# T01_411_Synth_v3.net
KiCad netlist of a schematic drawn in EAGLE
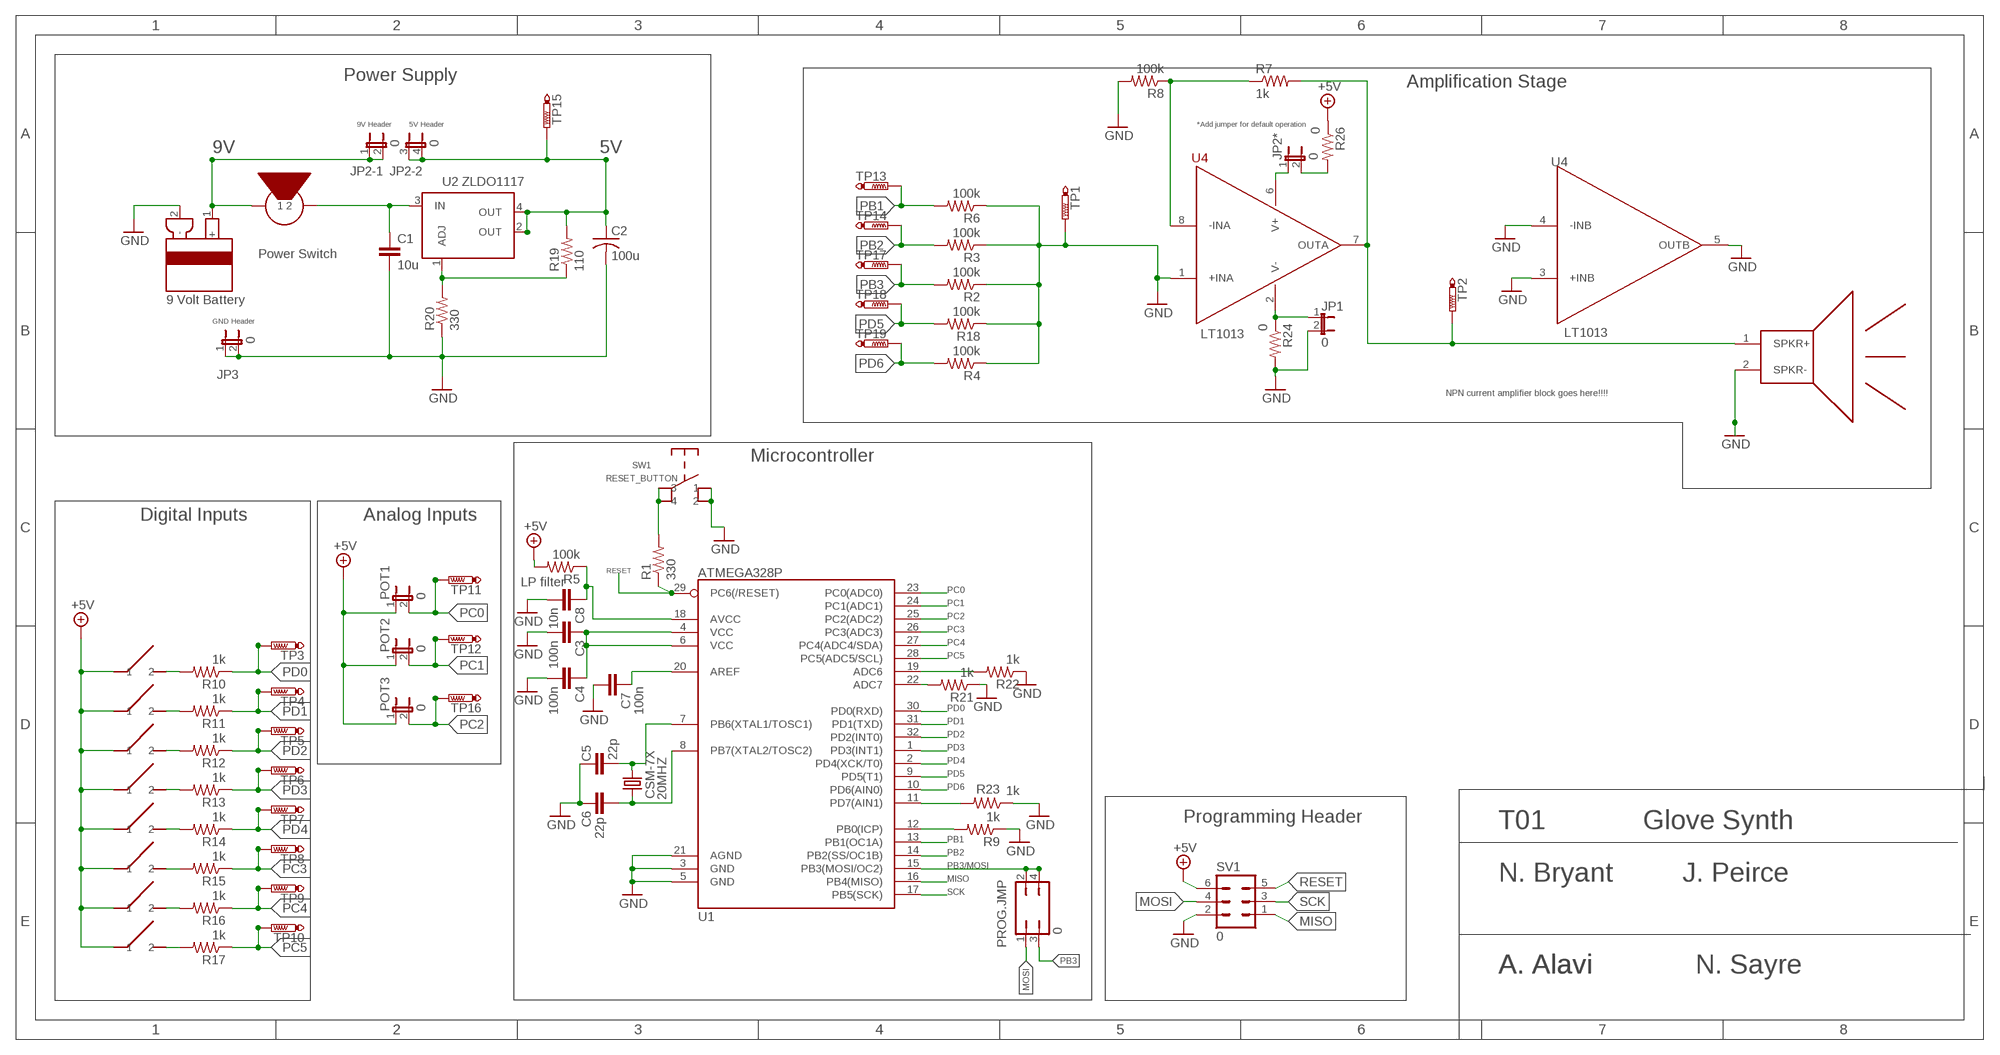
[diagram p0: schematic, sheet 1]

(export (version "E")
  (design (tool "Eeschema 10.0.6"))
  (components
    (comp (ref "20MHZ")
      (value "CSM-7X")
      (footprint "eagle-import:CSM-7X-DU")
      (libsource (lib "eagle-import") (part "CSM-7X-DU"))
    )
    (comp (ref "C1")
      (value "10u")
      (footprint "eagle-import:0603-CAP")
      (libsource (lib "eagle-import") (part "CAP0603-CAP"))
    )
    (comp (ref "C2")
      (value "100u")
      (footprint "eagle-import:C075-042X103")
      (libsource (lib "eagle-import") (part "C-US075-042X103"))
    )
    (comp (ref "C3")
      (value "100n")
      (footprint "eagle-import:0603-CAP")
      (libsource (lib "eagle-import") (part "CAP0603-CAP"))
    )
    (comp (ref "C4")
      (value "100n")
      (footprint "eagle-import:0603-CAP")
      (libsource (lib "eagle-import") (part "CAP0603-CAP"))
    )
    (comp (ref "C5")
      (value "22p")
      (footprint "eagle-import:0603-CAP")
      (libsource (lib "eagle-import") (part "CAP0603-CAP"))
    )
    (comp (ref "C6")
      (value "22p")
      (footprint "eagle-import:0603-CAP")
      (libsource (lib "eagle-import") (part "CAP0603-CAP"))
    )
    (comp (ref "C7")
      (value "100n")
      (footprint "eagle-import:0603-CAP")
      (libsource (lib "eagle-import") (part "CAP0603-CAP"))
    )
    (comp (ref "C8")
      (value "10n")
      (footprint "eagle-import:0603-CAP")
      (libsource (lib "eagle-import") (part "CAP0603-CAP"))
    )
    (comp (ref "JP1")
      (value "0")
      (footprint "eagle-import:JP1")
      (libsource (lib "eagle-import") (part "JP1E"))
    )
    (comp (ref "JP2")
      (value "0")
      (footprint "eagle-import:JP2Q")
      (libsource (lib "eagle-import") (part "JP2QE"))
    )
    (comp (ref "JP2*")
      (value "0")
      (footprint "eagle-import:JP1")
      (libsource (lib "eagle-import") (part "JP1E"))
    )
    (comp (ref "JP3")
      (value "0")
      (footprint "eagle-import:JP1")
      (libsource (lib "eagle-import") (part "JP1E"))
    )
    (comp (ref "POT1")
      (value "0")
      (footprint "eagle-import:JP1")
      (libsource (lib "eagle-import") (part "JP1E"))
    )
    (comp (ref "POT2")
      (value "0")
      (footprint "eagle-import:JP1")
      (libsource (lib "eagle-import") (part "JP1E"))
    )
    (comp (ref "POT3")
      (value "0")
      (footprint "eagle-import:JP1")
      (libsource (lib "eagle-import") (part "JP1E"))
    )
    (comp (ref "PROG.JMP")
      (value "0")
      (footprint "eagle-import:JP2Q")
      (libsource (lib "eagle-import") (part "JP2Q"))
    )
    (comp (ref "R1")
      (value "330")
      (footprint "eagle-import:0603-RES")
      (libsource (lib "eagle-import") (part "RESISTOR0603"))
    )
    (comp (ref "R2")
      (value "100k")
      (footprint "eagle-import:0603-RES")
      (libsource (lib "eagle-import") (part "RESISTOR0603"))
    )
    (comp (ref "R3")
      (value "100k")
      (footprint "eagle-import:0603-RES")
      (libsource (lib "eagle-import") (part "RESISTOR0603"))
    )
    (comp (ref "R4")
      (value "100k")
      (footprint "eagle-import:0603-RES")
      (libsource (lib "eagle-import") (part "RESISTOR0603"))
    )
    (comp (ref "R5")
      (value "100k")
      (footprint "eagle-import:0603-RES")
      (libsource (lib "eagle-import") (part "RESISTOR0603"))
    )
    (comp (ref "R6")
      (value "100k")
      (footprint "eagle-import:0603-RES")
      (libsource (lib "eagle-import") (part "RESISTOR0603"))
    )
    (comp (ref "R7")
      (value "1k")
      (footprint "eagle-import:0603-RES")
      (libsource (lib "eagle-import") (part "RESISTOR0603"))
    )
    (comp (ref "R8")
      (value "100k")
      (footprint "eagle-import:0603-RES")
      (libsource (lib "eagle-import") (part "RESISTOR0603"))
    )
    (comp (ref "R9")
      (value "1k")
      (footprint "eagle-import:0603-RES")
      (libsource (lib "eagle-import") (part "RESISTOR0603"))
    )
    (comp (ref "R10")
      (value "1k")
      (footprint "eagle-import:0603-RES")
      (libsource (lib "eagle-import") (part "RESISTOR0603"))
    )
    (comp (ref "R11")
      (value "1k")
      (footprint "eagle-import:0603-RES")
      (libsource (lib "eagle-import") (part "RESISTOR0603"))
    )
    (comp (ref "R12")
      (value "1k")
      (footprint "eagle-import:0603-RES")
      (libsource (lib "eagle-import") (part "RESISTOR0603"))
    )
    (comp (ref "R13")
      (value "1k")
      (footprint "eagle-import:0603-RES")
      (libsource (lib "eagle-import") (part "RESISTOR0603"))
    )
    (comp (ref "R14")
      (value "1k")
      (footprint "eagle-import:0603-RES")
      (libsource (lib "eagle-import") (part "RESISTOR0603"))
    )
    (comp (ref "R15")
      (value "1k")
      (footprint "eagle-import:0603-RES")
      (libsource (lib "eagle-import") (part "RESISTOR0603"))
    )
    (comp (ref "R16")
      (value "1k")
      (footprint "eagle-import:0603-RES")
      (libsource (lib "eagle-import") (part "RESISTOR0603"))
    )
    (comp (ref "R17")
      (value "1k")
      (footprint "eagle-import:0603-RES")
      (libsource (lib "eagle-import") (part "RESISTOR0603"))
    )
    (comp (ref "R18")
      (value "100k")
      (footprint "eagle-import:0603-RES")
      (libsource (lib "eagle-import") (part "RESISTOR0603"))
    )
    (comp (ref "R19")
      (value "110")
      (footprint "eagle-import:0603-RES")
      (libsource (lib "eagle-import") (part "RESISTOR0603"))
    )
    (comp (ref "R20")
      (value "330")
      (footprint "eagle-import:0603-RES")
      (libsource (lib "eagle-import") (part "RESISTOR0603"))
    )
    (comp (ref "R21")
      (value "1k")
      (footprint "eagle-import:0603-RES")
      (libsource (lib "eagle-import") (part "RESISTOR0603"))
    )
    (comp (ref "R22")
      (value "1k")
      (footprint "eagle-import:0603-RES")
      (libsource (lib "eagle-import") (part "RESISTOR0603"))
    )
    (comp (ref "R23")
      (value "1k")
      (footprint "eagle-import:0603-RES")
      (libsource (lib "eagle-import") (part "RESISTOR0603"))
    )
    (comp (ref "R24")
      (value "0")
      (footprint "eagle-import:0603-RES")
      (libsource (lib "eagle-import") (part "RESISTOR0603"))
    )
    (comp (ref "R26")
      (value "0")
      (footprint "eagle-import:0603-RES")
      (libsource (lib "eagle-import") (part "RESISTOR0603"))
    )
    (comp (ref "SV1")
      (value "0")
      (footprint "eagle-import:MA03-2")
      (libsource (lib "eagle-import") (part "MA03-2"))
    )
    (comp (ref "SW1")
      (value "RESET_BUTTON")
      (footprint "eagle-import:RESET_BUTTON")
      (libsource (lib "eagle-import") (part "RESET_BUTTON"))
    )
    (comp (ref "TP1")
      (value "PTR1B2,54")
      (footprint "eagle-import:B2,54")
      (libsource (lib "eagle-import") (part "PTR1B2,54"))
    )
    (comp (ref "TP2")
      (value "PTR1B2,54")
      (footprint "eagle-import:B2,54")
      (libsource (lib "eagle-import") (part "PTR1B2,54"))
    )
    (comp (ref "TP3")
      (value "PTR1B2,54")
      (footprint "eagle-import:B2,54")
      (libsource (lib "eagle-import") (part "PTR1B2,54"))
    )
    (comp (ref "TP4")
      (value "PTR1B2,54")
      (footprint "eagle-import:B2,54")
      (libsource (lib "eagle-import") (part "PTR1B2,54"))
    )
    (comp (ref "TP5")
      (value "PTR1B2,54")
      (footprint "eagle-import:B2,54")
      (libsource (lib "eagle-import") (part "PTR1B2,54"))
    )
    (comp (ref "TP6")
      (value "PTR1B2,54")
      (footprint "eagle-import:B2,54")
      (libsource (lib "eagle-import") (part "PTR1B2,54"))
    )
    (comp (ref "TP7")
      (value "PTR1B2,54")
      (footprint "eagle-import:B2,54")
      (libsource (lib "eagle-import") (part "PTR1B2,54"))
    )
    (comp (ref "TP8")
      (value "PTR1B2,54")
      (footprint "eagle-import:B2,54")
      (libsource (lib "eagle-import") (part "PTR1B2,54"))
    )
    (comp (ref "TP9")
      (value "PTR1B2,54")
      (footprint "eagle-import:B2,54")
      (libsource (lib "eagle-import") (part "PTR1B2,54"))
    )
    (comp (ref "TP10")
      (value "PTR1B2,54")
      (footprint "eagle-import:B2,54")
      (libsource (lib "eagle-import") (part "PTR1B2,54"))
    )
    (comp (ref "TP11")
      (value "PTR1B2,54")
      (footprint "eagle-import:B2,54")
      (libsource (lib "eagle-import") (part "PTR1B2,54"))
    )
    (comp (ref "TP12")
      (value "PTR1B2,54")
      (footprint "eagle-import:B2,54")
      (libsource (lib "eagle-import") (part "PTR1B2,54"))
    )
    (comp (ref "TP13")
      (value "PTR1B2,54")
      (footprint "eagle-import:B2,54")
      (libsource (lib "eagle-import") (part "PTR1B2,54"))
    )
    (comp (ref "TP14")
      (value "PTR1B2,54")
      (footprint "eagle-import:B2,54")
      (libsource (lib "eagle-import") (part "PTR1B2,54"))
    )
    (comp (ref "TP15")
      (value "PTR1B2,54")
      (footprint "eagle-import:B2,54")
      (libsource (lib "eagle-import") (part "PTR1B2,54"))
    )
    (comp (ref "TP16")
      (value "PTR1B2,54")
      (footprint "eagle-import:B2,54")
      (libsource (lib "eagle-import") (part "PTR1B2,54"))
    )
    (comp (ref "TP17")
      (value "PTR1B2,54")
      (footprint "eagle-import:B2,54")
      (libsource (lib "eagle-import") (part "PTR1B2,54"))
    )
    (comp (ref "TP18")
      (value "PTR1B2,54")
      (footprint "eagle-import:B2,54")
      (libsource (lib "eagle-import") (part "PTR1B2,54"))
    )
    (comp (ref "TP19")
      (value "PTR1B2,54")
      (footprint "eagle-import:B2,54")
      (libsource (lib "eagle-import") (part "PTR1B2,54"))
    )
    (comp (ref "U$1")
      (value "SPEAKER")
      (footprint "eagle-import:JP1")
      (libsource (lib "eagle-import") (part "SPEAKER"))
    )
    (comp (ref "U$7")
      (value "POWER_SWITCH")
      (footprint "eagle-import:JP1")
      (libsource (lib "eagle-import") (part "POWER_SWITCH"))
    )
    (comp (ref "U$8")
      (value "9VOLTBATTERY")
      (footprint "eagle-import:JP1")
      (libsource (lib "eagle-import") (part "9VOLTBATTERY"))
    )
    (comp (ref "U$11")
      (value "FINGER_BUTTON")
      (footprint "eagle-import:JP1")
      (libsource (lib "eagle-import") (part "FINGER_BUTTON"))
    )
    (comp (ref "U$12")
      (value "FINGER_BUTTON")
      (footprint "eagle-import:JP1")
      (libsource (lib "eagle-import") (part "FINGER_BUTTON"))
    )
    (comp (ref "U$13")
      (value "FINGER_BUTTON")
      (footprint "eagle-import:JP1")
      (libsource (lib "eagle-import") (part "FINGER_BUTTON"))
    )
    (comp (ref "U$14")
      (value "FINGER_BUTTON")
      (footprint "eagle-import:JP1")
      (libsource (lib "eagle-import") (part "FINGER_BUTTON"))
    )
    (comp (ref "U$15")
      (value "FINGER_BUTTON")
      (footprint "eagle-import:JP1")
      (libsource (lib "eagle-import") (part "FINGER_BUTTON"))
    )
    (comp (ref "U$16")
      (value "FINGER_BUTTON")
      (footprint "eagle-import:JP1")
      (libsource (lib "eagle-import") (part "FINGER_BUTTON"))
    )
    (comp (ref "U$17")
      (value "FINGER_BUTTON")
      (footprint "eagle-import:JP1")
      (libsource (lib "eagle-import") (part "FINGER_BUTTON"))
    )
    (comp (ref "U$18")
      (value "FINGER_BUTTON")
      (footprint "eagle-import:JP1")
      (libsource (lib "eagle-import") (part "FINGER_BUTTON"))
    )
    (comp (ref "U1")
      (value "ATMEGA328P")
      (footprint "eagle-import:TQFP32-08")
      (libsource (lib "eagle-import") (part "ATMEGA328_SMT"))
    )
    (comp (ref "U2")
      (value "ZLDO1117")
      (footprint "eagle-import:SOT223")
      (libsource (lib "eagle-import") (part "ZLDO1117"))
    )
    (comp (ref "U4")
      (value "LT1013")
      (footprint "eagle-import:SO08")
      (libsource (lib "eagle-import") (part "LT1013"))
    )
  )
  (nets
    (net (code "1") (name "+5V") (class "Default")
      (node (ref "POT1") (pin "1") (pinfunction "1_1") (pintype "passive"))
      (node (ref "POT2") (pin "1") (pinfunction "1_1") (pintype "passive"))
      (node (ref "POT3") (pin "1") (pinfunction "1_1") (pintype "passive"))
      (node (ref "R26") (pin "1") (pinfunction "1_1") (pintype "passive"))
      (node (ref "R5") (pin "2") (pinfunction "2_2") (pintype "passive"))
      (node (ref "SV1") (pin "6") (pinfunction "6_6") (pintype "passive"))
      (node (ref "U$11") (pin "1") (pinfunction "1_1") (pintype "bidirectional"))
      (node (ref "U$12") (pin "1") (pinfunction "1_1") (pintype "bidirectional"))
      (node (ref "U$13") (pin "1") (pinfunction "1_1") (pintype "bidirectional"))
      (node (ref "U$14") (pin "1") (pinfunction "1_1") (pintype "bidirectional"))
      (node (ref "U$15") (pin "1") (pinfunction "1_1") (pintype "bidirectional"))
      (node (ref "U$16") (pin "1") (pinfunction "1_1") (pintype "bidirectional"))
      (node (ref "U$17") (pin "1") (pinfunction "1_1") (pintype "bidirectional"))
      (node (ref "U$18") (pin "1") (pinfunction "1_1") (pintype "bidirectional"))
    )
    (net (code "2") (name "/5V") (class "Default")
      (node (ref "C2") (pin "1") (pinfunction "1_1") (pintype "passive"))
      (node (ref "JP2") (pin "3") (pinfunction "1_3") (pintype "passive"))
      (node (ref "JP2") (pin "4") (pinfunction "2_4") (pintype "passive"))
      (node (ref "R19") (pin "2") (pinfunction "2_2") (pintype "passive"))
      (node (ref "TP15") (pin "TP") (pinfunction "TP_TP") (pintype "input"))
      (node (ref "U2") (pin "2") (pinfunction "OUT_2") (pintype "bidirectional"))
      (node (ref "U2") (pin "4") (pinfunction "OUT_4") (pintype "bidirectional"))
    )
    (net (code "3") (name "/9V") (class "Default")
      (node (ref "JP2") (pin "1") (pinfunction "1_1") (pintype "passive"))
      (node (ref "JP2") (pin "2") (pinfunction "2_2") (pintype "passive"))
      (node (ref "U$7") (pin "1") (pinfunction "1_1") (pintype "bidirectional"))
      (node (ref "U$8") (pin "1") (pinfunction "+_1") (pintype "bidirectional"))
    )
    (net (code "4") (name "/PB3{slash}MOSI") (class "Default")
      (node (ref "PROG.JMP") (pin "2") (pinfunction "2_2") (pintype "passive"))
      (node (ref "PROG.JMP") (pin "4") (pinfunction "4_4") (pintype "passive"))
      (node (ref "U1") (pin "15") (pinfunction "PB3(MOSI/OC2)_15") (pintype "bidirectional"))
    )
    (net (code "5") (name "GND") (class "Default")
      (node (ref "C1") (pin "2") (pinfunction "2_2") (pintype "passive"))
      (node (ref "C2") (pin "2") (pinfunction "2_2") (pintype "passive"))
      (node (ref "C3") (pin "2") (pinfunction "2_2") (pintype "passive"))
      (node (ref "C4") (pin "2") (pinfunction "2_2") (pintype "passive"))
      (node (ref "C5") (pin "2") (pinfunction "2_2") (pintype "passive"))
      (node (ref "C6") (pin "2") (pinfunction "2_2") (pintype "passive"))
      (node (ref "C7") (pin "2") (pinfunction "2_2") (pintype "passive"))
      (node (ref "C8") (pin "2") (pinfunction "2_2") (pintype "passive"))
      (node (ref "JP1") (pin "2") (pinfunction "2_2") (pintype "passive"))
      (node (ref "JP3") (pin "1") (pinfunction "1_1") (pintype "passive"))
      (node (ref "JP3") (pin "2") (pinfunction "2_2") (pintype "passive"))
      (node (ref "R18") (pin "1") (pinfunction "1_1") (pintype "passive"))
      (node (ref "R2") (pin "1") (pinfunction "1_1") (pintype "passive"))
      (node (ref "R20") (pin "1") (pinfunction "1_1") (pintype "passive"))
      (node (ref "R21") (pin "1") (pinfunction "1_1") (pintype "passive"))
      (node (ref "R22") (pin "1") (pinfunction "1_1") (pintype "passive"))
      (node (ref "R23") (pin "1") (pinfunction "1_1") (pintype "passive"))
      (node (ref "R24") (pin "2") (pinfunction "2_2") (pintype "passive"))
      (node (ref "R3") (pin "1") (pinfunction "1_1") (pintype "passive"))
      (node (ref "R4") (pin "1") (pinfunction "1_1") (pintype "passive"))
      (node (ref "R6") (pin "1") (pinfunction "1_1") (pintype "passive"))
      (node (ref "R8") (pin "2") (pinfunction "2_2") (pintype "passive"))
      (node (ref "R9") (pin "1") (pinfunction "1_1") (pintype "passive"))
      (node (ref "SV1") (pin "2") (pinfunction "2_2") (pintype "passive"))
      (node (ref "SW1") (pin "1") (pinfunction "1_1") (pintype "bidirectional"))
      (node (ref "SW1") (pin "2") (pinfunction "2_2") (pintype "bidirectional"))
      (node (ref "TP1") (pin "TP") (pinfunction "TP_TP") (pintype "input"))
      (node (ref "U$1") (pin "2") (pinfunction "SPKR-_2") (pintype "bidirectional"))
      (node (ref "U$8") (pin "2") (pinfunction "-_2") (pintype "bidirectional"))
      (node (ref "U1") (pin "21") (pinfunction "AGND_21") (pintype "bidirectional"))
      (node (ref "U1") (pin "3") (pinfunction "GND_3") (pintype "bidirectional"))
      (node (ref "U1") (pin "5") (pinfunction "GND_5") (pintype "bidirectional"))
      (node (ref "U4") (pin "1") (pinfunction "+INA_1") (pintype "bidirectional"))
      (node (ref "U4") (pin "3") (pinfunction "+INB_3") (pintype "bidirectional"))
      (node (ref "U4") (pin "4") (pinfunction "-INB_4") (pintype "bidirectional"))
      (node (ref "U4") (pin "5") (pinfunction "OUTB_5") (pintype "bidirectional"))
    )
    (net (code "6") (name "MISO") (class "Default")
      (node (ref "SV1") (pin "1") (pinfunction "1_1") (pintype "passive"))
      (node (ref "U1") (pin "16") (pinfunction "PB4(MISO)_16") (pintype "bidirectional"))
    )
    (net (code "7") (name "MOSI") (class "Default")
      (node (ref "PROG.JMP") (pin "1") (pinfunction "1_1") (pintype "passive"))
      (node (ref "SV1") (pin "4") (pinfunction "4_4") (pintype "passive"))
    )
    (net (code "8") (name "Net-(C3-Pad1)") (class "Default")
      (node (ref "C3") (pin "1") (pinfunction "1_1") (pintype "passive"))
      (node (ref "C4") (pin "1") (pinfunction "1_1") (pintype "passive"))
      (node (ref "U1") (pin "4") (pinfunction "VCC_4") (pintype "bidirectional"))
      (node (ref "U1") (pin "6") (pinfunction "VCC_6") (pintype "bidirectional"))
    )
    (net (code "9") (name "Net-(JP2*-Pad2)") (class "Default")
      (node (ref "JP2*") (pin "2") (pinfunction "2_2") (pintype "passive"))
      (node (ref "R26") (pin "2") (pinfunction "2_2") (pintype "passive"))
    )
    (net (code "10") (name "Net-(R1-Pad2)") (class "Default")
      (node (ref "R1") (pin "2") (pinfunction "2_2") (pintype "passive"))
      (node (ref "SW1") (pin "3") (pinfunction "3_3") (pintype "bidirectional"))
      (node (ref "SW1") (pin "4") (pinfunction "4_4") (pintype "bidirectional"))
    )
    (net (code "11") (name "Net-(R10-Pad2)") (class "Default")
      (node (ref "R10") (pin "2") (pinfunction "2_2") (pintype "passive"))
      (node (ref "U$18") (pin "2") (pinfunction "2_2") (pintype "bidirectional"))
    )
    (net (code "12") (name "Net-(R11-Pad2)") (class "Default")
      (node (ref "R11") (pin "2") (pinfunction "2_2") (pintype "passive"))
      (node (ref "U$17") (pin "2") (pinfunction "2_2") (pintype "bidirectional"))
    )
    (net (code "13") (name "Net-(R12-Pad2)") (class "Default")
      (node (ref "R12") (pin "2") (pinfunction "2_2") (pintype "passive"))
      (node (ref "U$16") (pin "2") (pinfunction "2_2") (pintype "bidirectional"))
    )
    (net (code "14") (name "Net-(R13-Pad2)") (class "Default")
      (node (ref "R13") (pin "2") (pinfunction "2_2") (pintype "passive"))
      (node (ref "U$15") (pin "2") (pinfunction "2_2") (pintype "bidirectional"))
    )
    (net (code "15") (name "Net-(R14-Pad2)") (class "Default")
      (node (ref "R14") (pin "2") (pinfunction "2_2") (pintype "passive"))
      (node (ref "U$14") (pin "2") (pinfunction "2_2") (pintype "bidirectional"))
    )
    (net (code "16") (name "Net-(R15-Pad2)") (class "Default")
      (node (ref "R15") (pin "2") (pinfunction "2_2") (pintype "passive"))
      (node (ref "U$13") (pin "2") (pinfunction "2_2") (pintype "bidirectional"))
    )
    (net (code "17") (name "Net-(R16-Pad2)") (class "Default")
      (node (ref "R16") (pin "2") (pinfunction "2_2") (pintype "passive"))
      (node (ref "U$12") (pin "2") (pinfunction "2_2") (pintype "bidirectional"))
    )
    (net (code "18") (name "Net-(R17-Pad2)") (class "Default")
      (node (ref "R17") (pin "2") (pinfunction "2_2") (pintype "passive"))
      (node (ref "U$11") (pin "2") (pinfunction "2_2") (pintype "bidirectional"))
    )
    (net (code "19") (name "Net-(U$1-SPKR+)") (class "Default")
      (node (ref "R7") (pin "2") (pinfunction "2_2") (pintype "passive"))
      (node (ref "TP2") (pin "TP") (pinfunction "TP_TP") (pintype "input"))
      (node (ref "U$1") (pin "1") (pinfunction "SPKR+_1") (pintype "bidirectional"))
      (node (ref "U4") (pin "7") (pinfunction "OUTA_7") (pintype "bidirectional"))
    )
    (net (code "20") (name "Net-(U1-ADC6)") (class "Default")
      (node (ref "R22") (pin "2") (pinfunction "2_2") (pintype "passive"))
      (node (ref "U1") (pin "19") (pinfunction "ADC6_19") (pintype "bidirectional"))
    )
    (net (code "21") (name "Net-(U1-ADC7)") (class "Default")
      (node (ref "R21") (pin "2") (pinfunction "2_2") (pintype "passive"))
      (node (ref "U1") (pin "22") (pinfunction "ADC7_22") (pintype "bidirectional"))
    )
    (net (code "22") (name "Net-(U1-AREF)") (class "Default")
      (node (ref "C7") (pin "1") (pinfunction "1_1") (pintype "passive"))
      (node (ref "U1") (pin "20") (pinfunction "AREF_20") (pintype "bidirectional"))
    )
    (net (code "23") (name "Net-(U1-AVCC)") (class "Default")
      (node (ref "C8") (pin "1") (pinfunction "1_1") (pintype "passive"))
      (node (ref "R5") (pin "1") (pinfunction "1_1") (pintype "passive"))
      (node (ref "U1") (pin "18") (pinfunction "AVCC_18") (pintype "bidirectional"))
    )
    (net (code "24") (name "Net-(U1-PB0(ICP))") (class "Default")
      (node (ref "R9") (pin "2") (pinfunction "2_2") (pintype "passive"))
      (node (ref "U1") (pin "12") (pinfunction "PB0(ICP)_12") (pintype "bidirectional"))
    )
    (net (code "25") (name "Net-(U1-PB6(XTAL1{slash}TOSC1))") (class "Default")
      (node (ref "20MHZ") (pin "1") (pinfunction "1_1") (pintype "passive"))
      (node (ref "C5") (pin "1") (pinfunction "1_1") (pintype "passive"))
      (node (ref "U1") (pin "7") (pinfunction "PB6(XTAL1/TOSC1)_7") (pintype "bidirectional"))
    )
    (net (code "26") (name "Net-(U1-PB7(XTAL2{slash}TOSC2))") (class "Default")
      (node (ref "20MHZ") (pin "2") (pinfunction "2_2") (pintype "passive"))
      (node (ref "C6") (pin "1") (pinfunction "1_1") (pintype "passive"))
      (node (ref "U1") (pin "8") (pinfunction "PB7(XTAL2/TOSC2)_8") (pintype "bidirectional"))
    )
    (net (code "27") (name "Net-(U1-PD7(AIN1))") (class "Default")
      (node (ref "R23") (pin "2") (pinfunction "2_2") (pintype "passive"))
      (node (ref "U1") (pin "11") (pinfunction "PD7(AIN1)_11") (pintype "bidirectional"))
    )
    (net (code "28") (name "Net-(U2-ADJ)") (class "Default")
      (node (ref "R19") (pin "1") (pinfunction "1_1") (pintype "passive"))
      (node (ref "R20") (pin "2") (pinfunction "2_2") (pintype "passive"))
      (node (ref "U2") (pin "1") (pinfunction "ADJ_1") (pintype "bidirectional"))
    )
    (net (code "29") (name "Net-(U2-IN)") (class "Default")
      (node (ref "C1") (pin "1") (pinfunction "1_1") (pintype "passive"))
      (node (ref "U$7") (pin "2") (pinfunction "2_2") (pintype "bidirectional"))
      (node (ref "U2") (pin "3") (pinfunction "IN_3") (pintype "bidirectional"))
    )
    (net (code "30") (name "Net-(U4--INA)") (class "Default")
      (node (ref "R7") (pin "1") (pinfunction "1_1") (pintype "passive"))
      (node (ref "R8") (pin "1") (pinfunction "1_1") (pintype "passive"))
      (node (ref "U4") (pin "8") (pinfunction "-INA_8") (pintype "bidirectional"))
    )
    (net (code "31") (name "Net-(U4-V+)") (class "Default")
      (node (ref "JP2*") (pin "1") (pinfunction "1_1") (pintype "passive"))
      (node (ref "U4") (pin "6") (pinfunction "V+_6") (pintype "power_in"))
    )
    (net (code "32") (name "Net-(U4-V-)") (class "Default")
      (node (ref "JP1") (pin "1") (pinfunction "1_1") (pintype "passive"))
      (node (ref "R24") (pin "1") (pinfunction "1_1") (pintype "passive"))
      (node (ref "U4") (pin "2") (pinfunction "V-_2") (pintype "power_in"))
    )
    (net (code "33") (name "PB1") (class "Default")
      (node (ref "R6") (pin "2") (pinfunction "2_2") (pintype "passive"))
      (node (ref "TP13") (pin "TP") (pinfunction "TP_TP") (pintype "input"))
      (node (ref "U1") (pin "13") (pinfunction "PB1(OC1A)_13") (pintype "bidirectional"))
    )
    (net (code "34") (name "PB2") (class "Default")
      (node (ref "R3") (pin "2") (pinfunction "2_2") (pintype "passive"))
      (node (ref "TP14") (pin "TP") (pinfunction "TP_TP") (pintype "input"))
      (node (ref "U1") (pin "14") (pinfunction "PB2(SS/OC1B)_14") (pintype "bidirectional"))
    )
    (net (code "35") (name "PB3") (class "Default")
      (node (ref "PROG.JMP") (pin "3") (pinfunction "3_3") (pintype "passive"))
      (node (ref "R2") (pin "2") (pinfunction "2_2") (pintype "passive"))
      (node (ref "TP17") (pin "TP") (pinfunction "TP_TP") (pintype "input"))
    )
    (net (code "36") (name "PC0") (class "Default")
      (node (ref "POT1") (pin "2") (pinfunction "2_2") (pintype "passive"))
      (node (ref "TP11") (pin "TP") (pinfunction "TP_TP") (pintype "input"))
      (node (ref "U1") (pin "23") (pinfunction "PC0(ADC0)_23") (pintype "bidirectional"))
    )
    (net (code "37") (name "PC1") (class "Default")
      (node (ref "POT2") (pin "2") (pinfunction "2_2") (pintype "passive"))
      (node (ref "TP12") (pin "TP") (pinfunction "TP_TP") (pintype "input"))
      (node (ref "U1") (pin "24") (pinfunction "PC1(ADC1)_24") (pintype "bidirectional"))
    )
    (net (code "38") (name "PC2") (class "Default")
      (node (ref "POT3") (pin "2") (pinfunction "2_2") (pintype "passive"))
      (node (ref "TP16") (pin "TP") (pinfunction "TP_TP") (pintype "input"))
      (node (ref "U1") (pin "25") (pinfunction "PC2(ADC2)_25") (pintype "bidirectional"))
    )
    (net (code "39") (name "PC3") (class "Default")
      (node (ref "R15") (pin "1") (pinfunction "1_1") (pintype "passive"))
      (node (ref "TP8") (pin "TP") (pinfunction "TP_TP") (pintype "input"))
      (node (ref "U1") (pin "26") (pinfunction "PC3(ADC3)_26") (pintype "bidirectional"))
    )
    (net (code "40") (name "PC4") (class "Default")
      (node (ref "R16") (pin "1") (pinfunction "1_1") (pintype "passive"))
      (node (ref "TP9") (pin "TP") (pinfunction "TP_TP") (pintype "input"))
      (node (ref "U1") (pin "27") (pinfunction "PC4(ADC4/SDA)_27") (pintype "bidirectional"))
    )
    (net (code "41") (name "PC5") (class "Default")
      (node (ref "R17") (pin "1") (pinfunction "1_1") (pintype "passive"))
      (node (ref "TP10") (pin "TP") (pinfunction "TP_TP") (pintype "input"))
      (node (ref "U1") (pin "28") (pinfunction "PC5(ADC5/SCL)_28") (pintype "bidirectional"))
    )
    (net (code "42") (name "PD0") (class "Default")
      (node (ref "R10") (pin "1") (pinfunction "1_1") (pintype "passive"))
      (node (ref "TP3") (pin "TP") (pinfunction "TP_TP") (pintype "input"))
      (node (ref "U1") (pin "30") (pinfunction "PD0(RXD)_30") (pintype "bidirectional"))
    )
    (net (code "43") (name "PD1") (class "Default")
      (node (ref "R11") (pin "1") (pinfunction "1_1") (pintype "passive"))
      (node (ref "TP4") (pin "TP") (pinfunction "TP_TP") (pintype "input"))
      (node (ref "U1") (pin "31") (pinfunction "PD1(TXD)_31") (pintype "bidirectional"))
    )
    (net (code "44") (name "PD2") (class "Default")
      (node (ref "R12") (pin "1") (pinfunction "1_1") (pintype "passive"))
      (node (ref "TP5") (pin "TP") (pinfunction "TP_TP") (pintype "input"))
      (node (ref "U1") (pin "32") (pinfunction "PD2(INT0)_32") (pintype "bidirectional"))
    )
    (net (code "45") (name "PD3") (class "Default")
      (node (ref "R13") (pin "1") (pinfunction "1_1") (pintype "passive"))
      (node (ref "TP6") (pin "TP") (pinfunction "TP_TP") (pintype "input"))
      (node (ref "U1") (pin "1") (pinfunction "PD3(INT1)_1") (pintype "bidirectional"))
    )
    (net (code "46") (name "PD4") (class "Default")
      (node (ref "R14") (pin "1") (pinfunction "1_1") (pintype "passive"))
      (node (ref "TP7") (pin "TP") (pinfunction "TP_TP") (pintype "input"))
      (node (ref "U1") (pin "2") (pinfunction "PD4(XCK/T0)_2") (pintype "bidirectional"))
    )
    (net (code "47") (name "PD5") (class "Default")
      (node (ref "R18") (pin "2") (pinfunction "2_2") (pintype "passive"))
      (node (ref "TP18") (pin "TP") (pinfunction "TP_TP") (pintype "input"))
      (node (ref "U1") (pin "9") (pinfunction "PD5(T1)_9") (pintype "bidirectional"))
    )
    (net (code "48") (name "PD6") (class "Default")
      (node (ref "R4") (pin "2") (pinfunction "2_2") (pintype "passive"))
      (node (ref "TP19") (pin "TP") (pinfunction "TP_TP") (pintype "input"))
      (node (ref "U1") (pin "10") (pinfunction "PD6(AIN0)_10") (pintype "bidirectional"))
    )
    (net (code "49") (name "RESET") (class "Default")
      (node (ref "R1") (pin "1") (pinfunction "1_1") (pintype "passive"))
      (node (ref "SV1") (pin "5") (pinfunction "5_5") (pintype "passive"))
      (node (ref "U1") (pin "29") (pinfunction "PC6(/RESET)_29") (pintype "bidirectional"))
    )
    (net (code "50") (name "SCK") (class "Default")
      (node (ref "SV1") (pin "3") (pinfunction "3_3") (pintype "passive"))
      (node (ref "U1") (pin "17") (pinfunction "PB5(SCK)_17") (pintype "bidirectional"))
    )
  )
)
